# LKS_EVB_MCU081083088_V2_1.net
KiCad netlist of a schematic drawn in Altium Designer
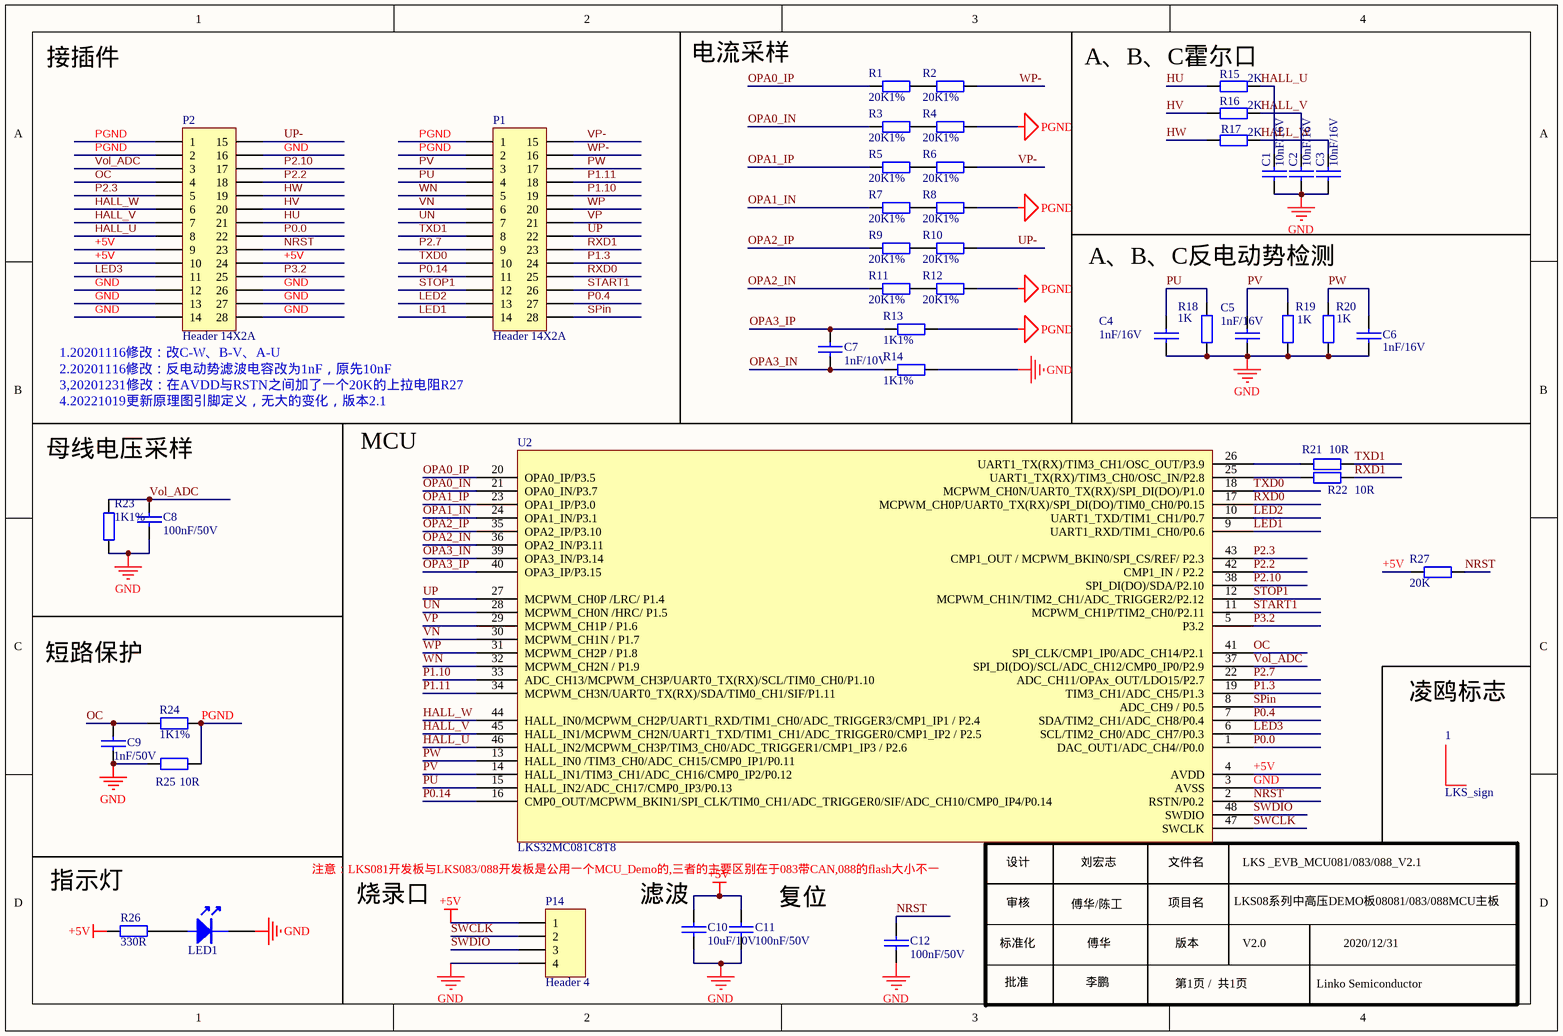
[diagram p0: LKS_EVB_MCU081083088_V2.1.SchDoc]

(export (version "E")
  (design (tool "Eeschema 10.0.6"))
  (components
    (comp (ref "1")
      (value "LKS_sign")
      (footprint "LKS_LOGO2")
      (libsource (lib "linko sch library") (part "LKS_sign"))
    )
    (comp (ref "C1")
      (value "10nF/16V")
      (footprint "0603C")
      (description "Capacitor")
      (libsource (lib "*") (part "CAP"))
    )
    (comp (ref "C2")
      (value "10nF/16V")
      (footprint "0603C")
      (description "Capacitor")
      (libsource (lib "*") (part "CAP"))
    )
    (comp (ref "C3")
      (value "10nF/16V")
      (footprint "0603C")
      (description "Capacitor")
      (libsource (lib "*") (part "CAP"))
    )
    (comp (ref "C4")
      (value "1nF/16V")
      (footprint "0603C")
      (description "Capacitor")
      (libsource (lib "*") (part "CAP"))
    )
    (comp (ref "C5")
      (value "1nF/16V")
      (footprint "0603C")
      (description "Capacitor")
      (libsource (lib "*") (part "CAP"))
    )
    (comp (ref "C6")
      (value "1nF/16V")
      (footprint "0603C")
      (description "Capacitor")
      (libsource (lib "*") (part "CAP"))
    )
    (comp (ref "C7")
      (value "1nF/10V")
      (footprint "0603C")
      (description "Capacitor")
      (libsource (lib "*") (part "C"))
    )
    (comp (ref "C8")
      (value "100nF/50V")
      (footprint "0603C")
      (description "Capacitor")
      (libsource (lib "*") (part "C"))
    )
    (comp (ref "C9")
      (value "1nF/50V")
      (footprint "0603C")
      (description "Capacitor")
      (libsource (lib "*") (part "C"))
    )
    (comp (ref "C10")
      (value "10uF/10V")
      (footprint "0603C")
      (description "Capacitor")
      (libsource (lib "*") (part "C"))
    )
    (comp (ref "C11")
      (value "100nF/50V")
      (footprint "0603C")
      (description "Capacitor")
      (libsource (lib "*") (part "C"))
    )
    (comp (ref "C12")
      (value "100nF/50V")
      (footprint "0603C")
      (description "Capacitor")
      (libsource (lib "*") (part "C"))
    )
    (comp (ref "LED1")
      (value "LED")
      (footprint "LED 0603R")
      (description "LED_Light")
      (libsource (lib "LINKO_V1.0") (part "LED"))
    )
    (comp (ref "P1")
      (value "Header 14X2A")
      (footprint "HDR2X14_CEN")
      (description "Header, 14-Pin, Dual row")
      (fields (field (name "PUBLISHER") "Altium Limited"))
      (libsource (lib "Miscellaneous Connectors") (part "Header 14X2A"))
    )
    (comp (ref "P2")
      (value "Header 14X2A")
      (footprint "HDR2X14_CEN")
      (description "Header, 14-Pin, Dual row")
      (fields (field (name "PUBLISHER") "Altium Limited"))
      (libsource (lib "Miscellaneous Connectors") (part "Header 14X2A"))
    )
    (comp (ref "P14")
      (value "Header 4")
      (footprint "HDR1X4")
      (description "Header, 4-Pin")
      (fields (field (name "PUBLISHER") "Altium Limited"))
      (libsource (lib "Miscellaneous Connectors") (part "Header 4"))
    )
    (comp (ref "R1")
      (value "20K1%")
      (footprint "0603R")
      (description "Resistor")
      (fields (field (name "PUBLISHER") "Altium Limited"))
      (libsource (lib "") (part "Res_2"))
    )
    (comp (ref "R2")
      (value "20K1%")
      (footprint "0603R")
      (description "Resistor")
      (fields (field (name "PUBLISHER") "Altium Limited"))
      (libsource (lib "") (part "Res_2"))
    )
    (comp (ref "R3")
      (value "20K1%")
      (footprint "0603R")
      (description "Resistor")
      (fields (field (name "PUBLISHER") "Altium Limited"))
      (libsource (lib "") (part "Res_2"))
    )
    (comp (ref "R4")
      (value "20K1%")
      (footprint "0603R")
      (description "Resistor")
      (fields (field (name "PUBLISHER") "Altium Limited"))
      (libsource (lib "") (part "Res_2"))
    )
    (comp (ref "R5")
      (value "20K1%")
      (footprint "0603R")
      (description "Resistor")
      (fields (field (name "PUBLISHER") "Altium Limited"))
      (libsource (lib "") (part "Res_2"))
    )
    (comp (ref "R6")
      (value "20K1%")
      (footprint "0603R")
      (description "Resistor")
      (fields (field (name "PUBLISHER") "Altium Limited"))
      (libsource (lib "") (part "Res_2"))
    )
    (comp (ref "R7")
      (value "20K1%")
      (footprint "0603R")
      (description "Resistor")
      (fields (field (name "PUBLISHER") "Altium Limited"))
      (libsource (lib "") (part "Res_2"))
    )
    (comp (ref "R8")
      (value "20K1%")
      (footprint "0603R")
      (description "Resistor")
      (fields (field (name "PUBLISHER") "Altium Limited"))
      (libsource (lib "") (part "Res_2"))
    )
    (comp (ref "R9")
      (value "20K1%")
      (footprint "0603R")
      (description "Resistor")
      (fields (field (name "PUBLISHER") "Altium Limited"))
      (libsource (lib "") (part "Res_2"))
    )
    (comp (ref "R10")
      (value "20K1%")
      (footprint "0603R")
      (description "Resistor")
      (fields (field (name "PUBLISHER") "Altium Limited"))
      (libsource (lib "") (part "Res_2"))
    )
    (comp (ref "R11")
      (value "20K1%")
      (footprint "0603R")
      (description "Resistor")
      (fields (field (name "PUBLISHER") "Altium Limited"))
      (libsource (lib "") (part "Res_2"))
    )
    (comp (ref "R12")
      (value "20K1%")
      (footprint "0603R")
      (description "Resistor")
      (fields (field (name "PUBLISHER") "Altium Limited"))
      (libsource (lib "") (part "Res_2"))
    )
    (comp (ref "R13")
      (value "1K1%")
      (footprint "0603R")
      (description "Resistor")
      (fields (field (name "PUBLISHER") "Altium Limited"))
      (libsource (lib "") (part "Res_2"))
    )
    (comp (ref "R14")
      (value "1K1%")
      (footprint "0603R")
      (description "Resistor")
      (fields (field (name "PUBLISHER") "Altium Limited"))
      (libsource (lib "") (part "Res_2"))
    )
    (comp (ref "R15")
      (value "2K")
      (footprint "0603R")
      (description "Resistor")
      (fields (field (name "PUBLISHER") "Altium Limited"))
      (libsource (lib "") (part "Res_3"))
    )
    (comp (ref "R16")
      (value "2K")
      (footprint "0603R")
      (description "Resistor")
      (fields (field (name "PUBLISHER") "Altium Limited"))
      (libsource (lib "") (part "Res_3"))
    )
    (comp (ref "R17")
      (value "2K")
      (footprint "0603R")
      (description "Resistor")
      (fields (field (name "PUBLISHER") "Altium Limited"))
      (libsource (lib "") (part "Res_3"))
    )
    (comp (ref "R18")
      (value "1K")
      (footprint "0603R")
      (description "Resistor")
      (fields (field (name "PUBLISHER") "Altium Limited"))
      (libsource (lib "") (part "Res_2"))
    )
    (comp (ref "R19")
      (value "1K")
      (footprint "0603R")
      (description "Resistor")
      (fields (field (name "PUBLISHER") "Altium Limited"))
      (libsource (lib "") (part "Res_2"))
    )
    (comp (ref "R20")
      (value "1K")
      (footprint "0603R")
      (description "Resistor")
      (fields (field (name "PUBLISHER") "Altium Limited"))
      (libsource (lib "") (part "Res_2"))
    )
    (comp (ref "R21")
      (value "10R")
      (footprint "0603R")
      (description "Resistor")
      (fields (field (name "PUBLISHER") "Altium Limited"))
      (libsource (lib "LINKO_V1.0") (part "Res"))
    )
    (comp (ref "R22")
      (value "10R")
      (footprint "0603R")
      (description "Resistor")
      (fields (field (name "PUBLISHER") "Altium Limited"))
      (libsource (lib "") (part "Res_1"))
    )
    (comp (ref "R23")
      (value "1K1%")
      (footprint "0603R")
      (description "Resistor")
      (fields (field (name "PUBLISHER") "Altium Limited"))
      (libsource (lib "") (part "Res_1"))
    )
    (comp (ref "R24")
      (value "1K1%")
      (footprint "0603R")
      (description "Resistor")
      (fields (field (name "PUBLISHER") "Altium Limited"))
      (libsource (lib "") (part "Res_3"))
    )
    (comp (ref "R25")
      (value "10R")
      (footprint "0603R")
      (description "Resistor")
      (fields (field (name "PUBLISHER") "Altium Limited"))
      (libsource (lib "") (part "Res_2"))
    )
    (comp (ref "R26")
      (value "330R")
      (footprint "0603R")
      (description "Resistor")
      (fields (field (name "PUBLISHER") "Altium Limited"))
      (libsource (lib "") (part "Res_1"))
    )
    (comp (ref "R27")
      (value "20K")
      (footprint "0603R")
      (description "Resistor")
      (fields (field (name "PUBLISHER") "Altium Limited"))
      (libsource (lib "") (part "Res_2"))
    )
    (comp (ref "U2")
      (value "LKS32MC081C8T8")
      (footprint "LINKO-081")
      (description "CHIP")
      (libsource (lib "LINKO_V1.0") (part "LKS32MC081C8T8"))
    )
  )
  (nets
    (net (code "1") (name "+5V") (class "Default")
      (node (ref "C10") (pin "2") (pinfunction "2_2") (pintype "passive"))
      (node (ref "C11") (pin "2") (pinfunction "2_2") (pintype "passive"))
      (node (ref "P14") (pin "1") (pinfunction "1_1") (pintype "passive"))
      (node (ref "P2") (pin "10") (pinfunction "10_10") (pintype "passive"))
      (node (ref "P2") (pin "24") (pinfunction "24_24") (pintype "passive"))
      (node (ref "P2") (pin "9") (pinfunction "9_9") (pintype "passive"))
      (node (ref "R26") (pin "1") (pinfunction "1_1") (pintype "passive"))
      (node (ref "R27") (pin "2") (pinfunction "2_2") (pintype "passive"))
      (node (ref "U2") (pin "4") (pinfunction "AVDD_4") (pintype "passive"))
    )
    (net (code "2") (name "/HALL_U") (class "Default")
      (node (ref "C1") (pin "1") (pinfunction "1_1") (pintype "passive"))
      (node (ref "P2") (pin "8") (pinfunction "8_8") (pintype "passive"))
      (node (ref "R15") (pin "2") (pinfunction "2_2") (pintype "passive"))
      (node (ref "U2") (pin "46") (pinfunction "HALL_IN2/MCPWM_CH3P/TIM3_CH0/ADC_TRIGGER1/CMP1_IP3_/_P2.6_46") (pintype "passive"))
    )
    (net (code "3") (name "/HALL_V") (class "Default")
      (node (ref "C2") (pin "1") (pinfunction "1_1") (pintype "passive"))
      (node (ref "P2") (pin "7") (pinfunction "7_7") (pintype "passive"))
      (node (ref "R16") (pin "2") (pinfunction "2_2") (pintype "passive"))
      (node (ref "U2") (pin "45") (pinfunction "HALL_IN1/MCPWM_CH2N/UART1_TXD/TIM1_CH1/ADC_TRIGGER0/CMP1_IP2_/_P2.5_45") (pintype "passive"))
    )
    (net (code "4") (name "/HALL_W") (class "Default")
      (node (ref "C3") (pin "1") (pinfunction "1_1") (pintype "passive"))
      (node (ref "P2") (pin "6") (pinfunction "6_6") (pintype "passive"))
      (node (ref "R17") (pin "2") (pinfunction "2_2") (pintype "passive"))
      (node (ref "U2") (pin "44") (pinfunction "HALL_IN0/MCPWM_CH2P/UART1_RXD/TIM1_CH0/ADC_TRIGGER3/CMP1_IP1_/_P2.4_44") (pintype "passive"))
    )
    (net (code "5") (name "/HU") (class "Default")
      (node (ref "P2") (pin "21") (pinfunction "21_21") (pintype "passive"))
      (node (ref "R15") (pin "1") (pinfunction "1_1") (pintype "passive"))
    )
    (net (code "6") (name "/HV") (class "Default")
      (node (ref "P2") (pin "20") (pinfunction "20_20") (pintype "passive"))
      (node (ref "R16") (pin "1") (pinfunction "1_1") (pintype "passive"))
    )
    (net (code "7") (name "/HW") (class "Default")
      (node (ref "P2") (pin "19") (pinfunction "19_19") (pintype "passive"))
      (node (ref "R17") (pin "1") (pinfunction "1_1") (pintype "passive"))
    )
    (net (code "8") (name "/LED1") (class "Default")
      (node (ref "P1") (pin "14") (pinfunction "14_14") (pintype "passive"))
      (node (ref "U2") (pin "9") (pinfunction "UART1_RXD/TIM1_CH0/P0.6_9") (pintype "passive"))
    )
    (net (code "9") (name "/LED2") (class "Default")
      (node (ref "P1") (pin "13") (pinfunction "13_13") (pintype "passive"))
      (node (ref "U2") (pin "10") (pinfunction "UART1_TXD/TIM1_CH1/P0.7_10") (pintype "passive"))
    )
    (net (code "10") (name "/LED3") (class "Default")
      (node (ref "P2") (pin "11") (pinfunction "11_11") (pintype "passive"))
      (node (ref "U2") (pin "6") (pinfunction "SCL/TIM2_CH0/ADC_CH7/P0.3_6") (pintype "passive"))
    )
    (net (code "11") (name "/NRST") (class "Default")
      (node (ref "C12") (pin "1") (pinfunction "1_1") (pintype "passive"))
      (node (ref "P2") (pin "23") (pinfunction "23_23") (pintype "passive"))
      (node (ref "R27") (pin "1") (pinfunction "1_1") (pintype "passive"))
      (node (ref "U2") (pin "2") (pinfunction "RSTN/P0.2_2") (pintype "passive"))
    )
    (net (code "12") (name "/OC") (class "Default")
      (node (ref "C9") (pin "2") (pinfunction "2_2") (pintype "passive"))
      (node (ref "P2") (pin "4") (pinfunction "4_4") (pintype "passive"))
      (node (ref "R24") (pin "1") (pinfunction "1_1") (pintype "passive"))
      (node (ref "U2") (pin "41") (pinfunction "SPI_CLK/CMP1_IP0/ADC_CH14/P2.1_41") (pintype "passive"))
    )
    (net (code "13") (name "/OPA0_IN") (class "Default")
      (node (ref "R3") (pin "2") (pinfunction "2_2") (pintype "passive"))
      (node (ref "U2") (pin "21") (pinfunction "OPA0_IN/P3.7_21") (pintype "passive"))
    )
    (net (code "14") (name "/OPA0_IP") (class "Default")
      (node (ref "R1") (pin "2") (pinfunction "2_2") (pintype "passive"))
      (node (ref "U2") (pin "20") (pinfunction "OPA0_IP/P3.5_20") (pintype "passive"))
    )
    (net (code "15") (name "/OPA1_IN") (class "Default")
      (node (ref "R7") (pin "2") (pinfunction "2_2") (pintype "passive"))
      (node (ref "U2") (pin "24") (pinfunction "OPA1_IN/P3.1_24") (pintype "passive"))
    )
    (net (code "16") (name "/OPA1_IP") (class "Default")
      (node (ref "R5") (pin "2") (pinfunction "2_2") (pintype "passive"))
      (node (ref "U2") (pin "23") (pinfunction "OPA1_IP/P3.0_23") (pintype "passive"))
    )
    (net (code "17") (name "/OPA2_IN") (class "Default")
      (node (ref "R11") (pin "2") (pinfunction "2_2") (pintype "passive"))
      (node (ref "U2") (pin "36") (pinfunction "OPA2_IN/P3.11_36") (pintype "passive"))
    )
    (net (code "18") (name "/OPA2_IP") (class "Default")
      (node (ref "R9") (pin "2") (pinfunction "2_2") (pintype "passive"))
      (node (ref "U2") (pin "35") (pinfunction "OPA2_IP/P3.10_35") (pintype "passive"))
    )
    (net (code "19") (name "/OPA3_IN") (class "Default")
      (node (ref "C7") (pin "2") (pinfunction "2_2") (pintype "passive"))
      (node (ref "R14") (pin "2") (pinfunction "2_2") (pintype "passive"))
      (node (ref "U2") (pin "39") (pinfunction "OPA3_IN/P3.14_39") (pintype "passive"))
    )
    (net (code "20") (name "/OPA3_IP") (class "Default")
      (node (ref "C7") (pin "1") (pinfunction "1_1") (pintype "passive"))
      (node (ref "R13") (pin "2") (pinfunction "2_2") (pintype "passive"))
      (node (ref "U2") (pin "40") (pinfunction "OPA3_IP/P3.15_40") (pintype "passive"))
    )
    (net (code "21") (name "/P0.0") (class "Default")
      (node (ref "P2") (pin "22") (pinfunction "22_22") (pintype "passive"))
      (node (ref "U2") (pin "1") (pinfunction "DAC_OUT1/ADC_CH4//P0.0_1") (pintype "passive"))
    )
    (net (code "22") (name "/P0.4") (class "Default")
      (node (ref "P1") (pin "27") (pinfunction "27_27") (pintype "passive"))
      (node (ref "U2") (pin "7") (pinfunction "SDA/TIM2_CH1/ADC_CH8/P0.4_7") (pintype "passive"))
    )
    (net (code "23") (name "/P0.14") (class "Default")
      (node (ref "P1") (pin "11") (pinfunction "11_11") (pintype "passive"))
      (node (ref "U2") (pin "16") (pinfunction "CMP0_OUT/MCPWM_BKIN1/SPI_CLK/TIM0_CH1/ADC_TRIGGER0/SIF/ADC_CH10/CMP0_IP4/P0.14_16") (pintype "passive"))
    )
    (net (code "24") (name "/P1.3") (class "Default")
      (node (ref "P1") (pin "24") (pinfunction "24_24") (pintype "passive"))
      (node (ref "U2") (pin "19") (pinfunction "TIM3_CH1/ADC_CH5/P1.3_19") (pintype "passive"))
    )
    (net (code "25") (name "/P1.10") (class "Default")
      (node (ref "P1") (pin "19") (pinfunction "19_19") (pintype "passive"))
      (node (ref "U2") (pin "33") (pinfunction "ADC_CH13/MCPWM_CH3P/UART0_TX(RX)/SCL/TIM0_CH0/P1.10_33") (pintype "passive"))
    )
    (net (code "26") (name "/P1.11") (class "Default")
      (node (ref "P1") (pin "18") (pinfunction "18_18") (pintype "passive"))
      (node (ref "U2") (pin "34") (pinfunction "MCPWM_CH3N/UART0_TX(RX)/SDA/TIM0_CH1/SIF/P1.11_34") (pintype "passive"))
    )
    (net (code "27") (name "/P2.2") (class "Default")
      (node (ref "P2") (pin "18") (pinfunction "18_18") (pintype "passive"))
      (node (ref "U2") (pin "42") (pinfunction "CMP1_IN_/_P2.2_42") (pintype "passive"))
    )
    (net (code "28") (name "/P2.3") (class "Default")
      (node (ref "P2") (pin "5") (pinfunction "5_5") (pintype "passive"))
      (node (ref "U2") (pin "43") (pinfunction "CMP1_OUT_/_MCPWM_BKIN0/SPI_CS/REF/_P2.3_43") (pintype "passive"))
    )
    (net (code "29") (name "/P2.7") (class "Default")
      (node (ref "P1") (pin "9") (pinfunction "9_9") (pintype "passive"))
      (node (ref "U2") (pin "22") (pinfunction "ADC_CH11/OPAx_OUT/LDO15/P2.7_22") (pintype "passive"))
    )
    (net (code "30") (name "/P2.10") (class "Default")
      (node (ref "P2") (pin "17") (pinfunction "17_17") (pintype "passive"))
      (node (ref "U2") (pin "38") (pinfunction "SPI_DI(DO)/SDA/P2.10_38") (pintype "passive"))
    )
    (net (code "31") (name "/P3.2") (class "Default")
      (node (ref "P2") (pin "25") (pinfunction "25_25") (pintype "passive"))
      (node (ref "U2") (pin "5") (pinfunction "P3.2_5") (pintype "passive"))
    )
    (net (code "32") (name "/PU") (class "Default")
      (node (ref "C4") (pin "1") (pinfunction "1_1") (pintype "passive"))
      (node (ref "P1") (pin "4") (pinfunction "4_4") (pintype "passive"))
      (node (ref "R18") (pin "1") (pinfunction "1_1") (pintype "passive"))
      (node (ref "U2") (pin "15") (pinfunction "HALL_IN2/ADC_CH17/CMP0_IP3/P0.13_15") (pintype "passive"))
    )
    (net (code "33") (name "/PV") (class "Default")
      (node (ref "C5") (pin "1") (pinfunction "1_1") (pintype "passive"))
      (node (ref "P1") (pin "3") (pinfunction "3_3") (pintype "passive"))
      (node (ref "R19") (pin "1") (pinfunction "1_1") (pintype "passive"))
      (node (ref "U2") (pin "14") (pinfunction "HALL_IN1/TIM3_CH1/ADC_CH16/CMP0_IP2/P0.12_14") (pintype "passive"))
    )
    (net (code "34") (name "/PW") (class "Default")
      (node (ref "C6") (pin "1") (pinfunction "1_1") (pintype "passive"))
      (node (ref "P1") (pin "17") (pinfunction "17_17") (pintype "passive"))
      (node (ref "R20") (pin "1") (pinfunction "1_1") (pintype "passive"))
      (node (ref "U2") (pin "13") (pinfunction "HALL_IN0_/TIM3_CH0/ADC_CH15/CMP0_IP1/P0.11_13") (pintype "passive"))
    )
    (net (code "35") (name "/RXD0") (class "Default")
      (node (ref "P1") (pin "25") (pinfunction "25_25") (pintype "passive"))
      (node (ref "U2") (pin "17") (pinfunction "MCPWM_CH0P/UART0_TX(RX)/SPI_DI(DO)/TIM0_CH0/P0.15_17") (pintype "passive"))
    )
    (net (code "36") (name "/RXD1") (class "Default")
      (node (ref "P1") (pin "23") (pinfunction "23_23") (pintype "passive"))
      (node (ref "R22") (pin "2") (pinfunction "2_2") (pintype "passive"))
    )
    (net (code "37") (name "/SPin") (class "Default")
      (node (ref "P1") (pin "28") (pinfunction "28_28") (pintype "passive"))
      (node (ref "U2") (pin "8") (pinfunction "ADC_CH9_/_P0.5_8") (pintype "passive"))
    )
    (net (code "38") (name "/START1") (class "Default")
      (node (ref "P1") (pin "26") (pinfunction "26_26") (pintype "passive"))
      (node (ref "U2") (pin "11") (pinfunction "MCPWM_CH1P/TIM2_CH0/P2.11_11") (pintype "passive"))
    )
    (net (code "39") (name "/STOP1") (class "Default")
      (node (ref "P1") (pin "12") (pinfunction "12_12") (pintype "passive"))
      (node (ref "U2") (pin "12") (pinfunction "MCPWM_CH1N/TIM2_CH1/ADC_TRIGGER2/P2.12_12") (pintype "passive"))
    )
    (net (code "40") (name "/SWCLK") (class "Default")
      (node (ref "P14") (pin "2") (pinfunction "2_2") (pintype "passive"))
      (node (ref "U2") (pin "47") (pinfunction "SWCLK_47") (pintype "passive"))
    )
    (net (code "41") (name "/SWDIO") (class "Default")
      (node (ref "P14") (pin "3") (pinfunction "3_3") (pintype "passive"))
      (node (ref "U2") (pin "48") (pinfunction "SWDIO_48") (pintype "passive"))
    )
    (net (code "42") (name "/TXD0") (class "Default")
      (node (ref "P1") (pin "10") (pinfunction "10_10") (pintype "passive"))
      (node (ref "U2") (pin "18") (pinfunction "MCPWM_CH0N/UART0_TX(RX)/SPI_DI(DO)/P1.0_18") (pintype "passive"))
    )
    (net (code "43") (name "/TXD1") (class "Default")
      (node (ref "P1") (pin "8") (pinfunction "8_8") (pintype "passive"))
      (node (ref "R21") (pin "1") (pinfunction "1_1") (pintype "passive"))
    )
    (net (code "44") (name "/UN") (class "Default")
      (node (ref "P1") (pin "7") (pinfunction "7_7") (pintype "passive"))
      (node (ref "U2") (pin "28") (pinfunction "MCPWM_CH0N_/HRC/_P1.5_28") (pintype "passive"))
    )
    (net (code "45") (name "/UP") (class "Default")
      (node (ref "P1") (pin "22") (pinfunction "22_22") (pintype "passive"))
      (node (ref "U2") (pin "27") (pinfunction "MCPWM_CH0P_/LRC/_P1.4_27") (pintype "passive"))
    )
    (net (code "46") (name "/UP-") (class "Default")
      (node (ref "P2") (pin "15") (pinfunction "15_15") (pintype "passive"))
      (node (ref "R10") (pin "1") (pinfunction "1_1") (pintype "passive"))
    )
    (net (code "47") (name "/VN") (class "Default")
      (node (ref "P1") (pin "6") (pinfunction "6_6") (pintype "passive"))
      (node (ref "U2") (pin "30") (pinfunction "MCPWM_CH1N_/_P1.7_30") (pintype "passive"))
    )
    (net (code "48") (name "/VP") (class "Default")
      (node (ref "P1") (pin "21") (pinfunction "21_21") (pintype "passive"))
      (node (ref "U2") (pin "29") (pinfunction "MCPWM_CH1P_/_P1.6_29") (pintype "passive"))
    )
    (net (code "49") (name "/VP-") (class "Default")
      (node (ref "P1") (pin "15") (pinfunction "15_15") (pintype "passive"))
      (node (ref "R6") (pin "1") (pinfunction "1_1") (pintype "passive"))
    )
    (net (code "50") (name "/Vol_ADC") (class "Default")
      (node (ref "C8") (pin "2") (pinfunction "2_2") (pintype "passive"))
      (node (ref "P2") (pin "3") (pinfunction "3_3") (pintype "passive"))
      (node (ref "R23") (pin "2") (pinfunction "2_2") (pintype "passive"))
      (node (ref "U2") (pin "37") (pinfunction "SPI_DI(DO)/SCL/ADC_CH12/CMP0_IP0/P2.9_37") (pintype "passive"))
    )
    (net (code "51") (name "/WN") (class "Default")
      (node (ref "P1") (pin "5") (pinfunction "5_5") (pintype "passive"))
      (node (ref "U2") (pin "32") (pinfunction "MCPWM_CH2N_/_P1.9_32") (pintype "passive"))
    )
    (net (code "52") (name "/WP") (class "Default")
      (node (ref "P1") (pin "20") (pinfunction "20_20") (pintype "passive"))
      (node (ref "U2") (pin "31") (pinfunction "MCPWM_CH2P_/_P1.8_31") (pintype "passive"))
    )
    (net (code "53") (name "/WP-") (class "Default")
      (node (ref "P1") (pin "16") (pinfunction "16_16") (pintype "passive"))
      (node (ref "R2") (pin "1") (pinfunction "1_1") (pintype "passive"))
    )
    (net (code "54") (name "GND") (class "Default")
      (node (ref "C1") (pin "2") (pinfunction "2_2") (pintype "passive"))
      (node (ref "C10") (pin "1") (pinfunction "1_1") (pintype "passive"))
      (node (ref "C11") (pin "1") (pinfunction "1_1") (pintype "passive"))
      (node (ref "C12") (pin "2") (pinfunction "2_2") (pintype "passive"))
      (node (ref "C2") (pin "2") (pinfunction "2_2") (pintype "passive"))
      (node (ref "C3") (pin "2") (pinfunction "2_2") (pintype "passive"))
      (node (ref "C4") (pin "2") (pinfunction "2_2") (pintype "passive"))
      (node (ref "C5") (pin "2") (pinfunction "2_2") (pintype "passive"))
      (node (ref "C6") (pin "2") (pinfunction "2_2") (pintype "passive"))
      (node (ref "C8") (pin "1") (pinfunction "1_1") (pintype "passive"))
      (node (ref "C9") (pin "1") (pinfunction "1_1") (pintype "passive"))
      (node (ref "LED1") (pin "2") (pinfunction "K_2") (pintype "passive"))
      (node (ref "P14") (pin "4") (pinfunction "4_4") (pintype "passive"))
      (node (ref "P2") (pin "12") (pinfunction "12_12") (pintype "passive"))
      (node (ref "P2") (pin "13") (pinfunction "13_13") (pintype "passive"))
      (node (ref "P2") (pin "14") (pinfunction "14_14") (pintype "passive"))
      (node (ref "P2") (pin "16") (pinfunction "16_16") (pintype "passive"))
      (node (ref "P2") (pin "26") (pinfunction "26_26") (pintype "passive"))
      (node (ref "P2") (pin "27") (pinfunction "27_27") (pintype "passive"))
      (node (ref "P2") (pin "28") (pinfunction "28_28") (pintype "passive"))
      (node (ref "R14") (pin "1") (pinfunction "1_1") (pintype "passive"))
      (node (ref "R18") (pin "2") (pinfunction "2_2") (pintype "passive"))
      (node (ref "R19") (pin "2") (pinfunction "2_2") (pintype "passive"))
      (node (ref "R20") (pin "2") (pinfunction "2_2") (pintype "passive"))
      (node (ref "R23") (pin "1") (pinfunction "1_1") (pintype "passive"))
      (node (ref "R25") (pin "2") (pinfunction "2_2") (pintype "passive"))
      (node (ref "U2") (pin "3") (pinfunction "AVSS_3") (pintype "passive"))
    )
    (net (code "55") (name "Net-(LED1-A)") (class "Default")
      (node (ref "LED1") (pin "1") (pinfunction "A_1") (pintype "passive"))
      (node (ref "R26") (pin "2") (pinfunction "2_2") (pintype "passive"))
    )
    (net (code "56") (name "Net-(R1-Pad1)") (class "Default")
      (node (ref "R1") (pin "1") (pinfunction "1_1") (pintype "passive"))
      (node (ref "R2") (pin "2") (pinfunction "2_2") (pintype "passive"))
    )
    (net (code "57") (name "Net-(R3-Pad1)") (class "Default")
      (node (ref "R3") (pin "1") (pinfunction "1_1") (pintype "passive"))
      (node (ref "R4") (pin "2") (pinfunction "2_2") (pintype "passive"))
    )
    (net (code "58") (name "Net-(R5-Pad1)") (class "Default")
      (node (ref "R5") (pin "1") (pinfunction "1_1") (pintype "passive"))
      (node (ref "R6") (pin "2") (pinfunction "2_2") (pintype "passive"))
    )
    (net (code "59") (name "Net-(R7-Pad1)") (class "Default")
      (node (ref "R7") (pin "1") (pinfunction "1_1") (pintype "passive"))
      (node (ref "R8") (pin "2") (pinfunction "2_2") (pintype "passive"))
    )
    (net (code "60") (name "Net-(R10-Pad2)") (class "Default")
      (node (ref "R10") (pin "2") (pinfunction "2_2") (pintype "passive"))
      (node (ref "R9") (pin "1") (pinfunction "1_1") (pintype "passive"))
    )
    (net (code "61") (name "Net-(R11-Pad1)") (class "Default")
      (node (ref "R11") (pin "1") (pinfunction "1_1") (pintype "passive"))
      (node (ref "R12") (pin "2") (pinfunction "2_2") (pintype "passive"))
    )
    (net (code "62") (name "Net-(U2-UART1_TX(RX){slash}TIM3_CH0{slash}OSC_IN{slash}P2.8)") (class "Default")
      (node (ref "R22") (pin "1") (pinfunction "1_1") (pintype "passive"))
      (node (ref "U2") (pin "25") (pinfunction "UART1_TX(RX)/TIM3_CH0/OSC_IN/P2.8_25") (pintype "passive"))
    )
    (net (code "63") (name "Net-(U2-UART1_TX(RX){slash}TIM3_CH1{slash}OSC_OUT{slash}P3.9)") (class "Default")
      (node (ref "R21") (pin "2") (pinfunction "2_2") (pintype "passive"))
      (node (ref "U2") (pin "26") (pinfunction "UART1_TX(RX)/TIM3_CH1/OSC_OUT/P3.9_26") (pintype "passive"))
    )
    (net (code "64") (name "PGND") (class "Default")
      (node (ref "P1") (pin "1") (pinfunction "1_1") (pintype "passive"))
      (node (ref "P1") (pin "2") (pinfunction "2_2") (pintype "passive"))
      (node (ref "P2") (pin "1") (pinfunction "1_1") (pintype "passive"))
      (node (ref "P2") (pin "2") (pinfunction "2_2") (pintype "passive"))
      (node (ref "R12") (pin "1") (pinfunction "1_1") (pintype "passive"))
      (node (ref "R13") (pin "1") (pinfunction "1_1") (pintype "passive"))
      (node (ref "R24") (pin "2") (pinfunction "2_2") (pintype "passive"))
      (node (ref "R25") (pin "1") (pinfunction "1_1") (pintype "passive"))
      (node (ref "R4") (pin "1") (pinfunction "1_1") (pintype "passive"))
      (node (ref "R8") (pin "1") (pinfunction "1_1") (pintype "passive"))
    )
  )
)
